# H_BRIDGE.net
KiCad netlist of a schematic drawn in Altium Designer
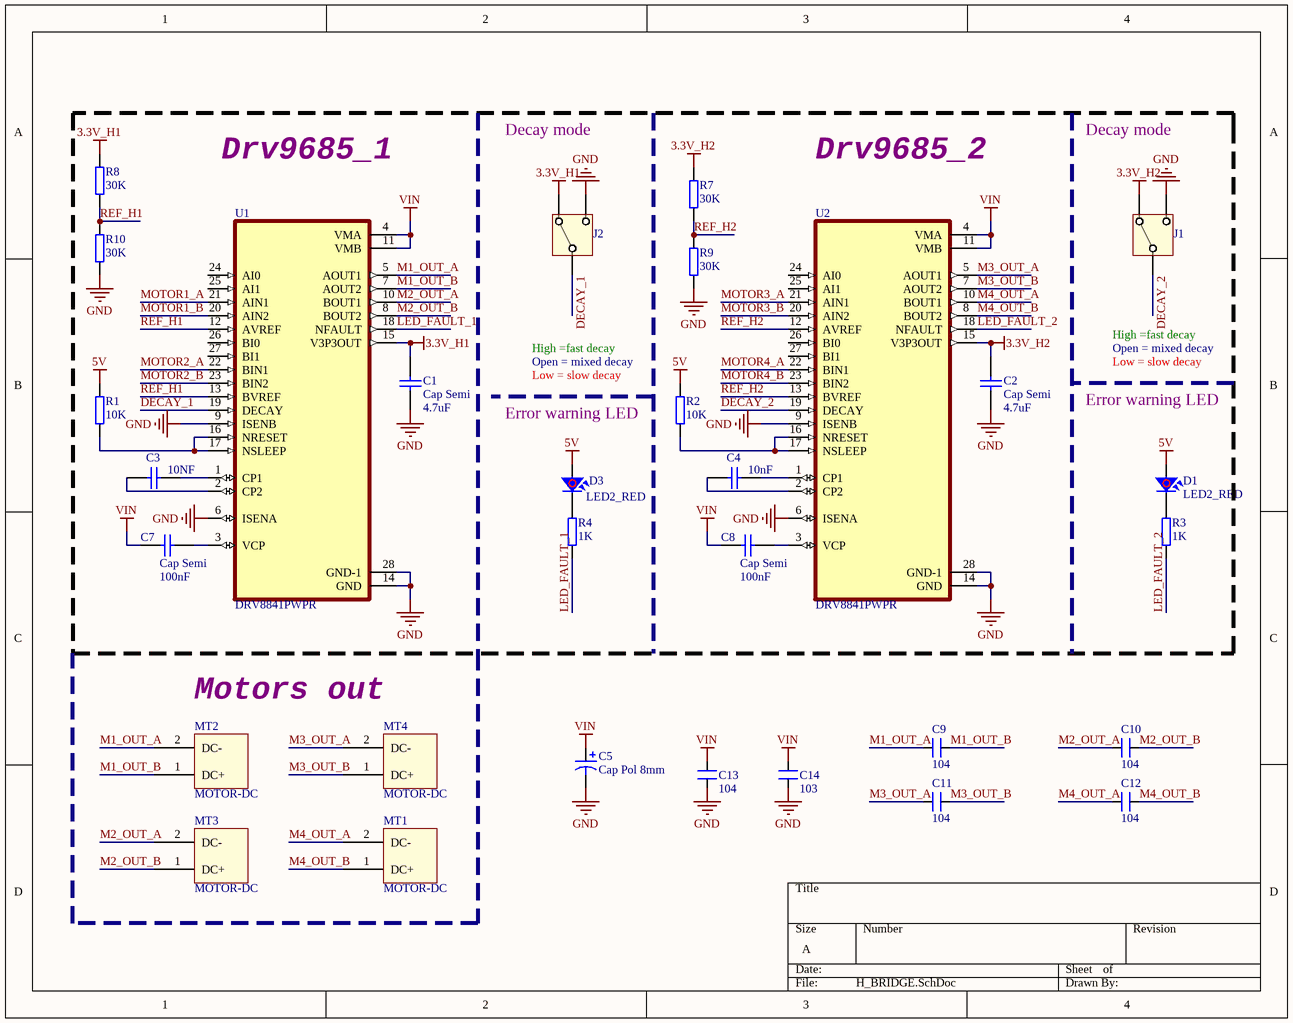
[diagram p0: H_BRIDGE.SchDoc]

(export (version "E")
  (design (tool "Eeschema 10.0.6"))
  (components
    (comp (ref "C1")
      (value "Cap Semi")
      (footprint "SMT0603")
      (description "CAP SM 0603 X5R 4.7uF 10%")
      (fields (field (name "TOLERANCE") "±10%") (field (name "ALTIUM_VALUE") "4.7uF"))
      (libsource (lib "electronpowered") (part "CAP-SM-0603-X5R-4.7uF"))
    )
    (comp (ref "C2")
      (value "Cap Semi")
      (footprint "SMT0603")
      (description "CAP SM 0603 X5R 4.7uF 10%")
      (fields (field (name "TOLERANCE") "±10%") (field (name "ALTIUM_VALUE") "4.7uF"))
      (libsource (lib "electronpowered") (part "CAP-SM-0603-X5R-4.7uF"))
    )
    (comp (ref "C3")
      (value "10NF")
      (footprint "SMT0603")
      (description "CAP SM 0603 X5R 10uF 10%")
      (fields (field (name "TOLERANCE") "±10%") (field (name "Comment") "Cap Semi"))
      (libsource (lib "electronpowered") (part "CAP-SM-0603-X5R-10uF"))
    )
    (comp (ref "C4")
      (value "10nF")
      (footprint "SMT0603")
      (description "CAP SM 0603 X5R 10uF 10%")
      (fields (field (name "TOLERANCE") "±10%") (field (name "Comment") "Cap Semi"))
      (libsource (lib "electronpowered") (part "CAP-SM-0603-X5R-10uF"))
    )
    (comp (ref "C5")
      (value "Cap Pol 8mm")
      (footprint "C10mm")
      (description "Polarized Capacitor (Axial)")
      (fields (field (name "PUBLISHER") "Altium Limited"))
      (libsource (lib "My Library") (part "Cap Pol 8mm"))
    )
    (comp (ref "C7")
      (value "Cap Semi")
      (footprint "SMT0603")
      (description "CAP SM 0603 X7R 100nF 10%")
      (fields (field (name "TOLERANCE") "±10%") (field (name "ALTIUM_VALUE") "100nF"))
      (libsource (lib "electronpowered") (part "CAP-SM-0603-X7R-100nF"))
    )
    (comp (ref "C8")
      (value "Cap Semi")
      (footprint "SMT0603")
      (description "CAP SM 0603 X7R 100nF 10%")
      (fields (field (name "TOLERANCE") "±10%") (field (name "ALTIUM_VALUE") "100nF"))
      (libsource (lib "electronpowered") (part "CAP-SM-0603-X7R-100nF"))
    )
    (comp (ref "C9")
      (value "104")
      (footprint "SM-0805")
      (description "Cap SMD")
      (libsource (lib "My Library") (part "CM"))
    )
    (comp (ref "C10")
      (value "104")
      (footprint "SM-0805")
      (description "Cap SMD")
      (libsource (lib "My Library") (part "CM"))
    )
    (comp (ref "C11")
      (value "104")
      (footprint "SM-0805")
      (description "Cap SMD")
      (libsource (lib "My Library") (part "CM"))
    )
    (comp (ref "C12")
      (value "104")
      (footprint "SM-0805")
      (description "Cap SMD")
      (libsource (lib "My Library") (part "CM"))
    )
    (comp (ref "C13")
      (value "104")
      (footprint "SM-0805")
      (description "Cap SMD")
      (libsource (lib "My Library") (part "CM"))
    )
    (comp (ref "C14")
      (value "103")
      (footprint "SM-0805")
      (description "Cap SMD")
      (libsource (lib "My Library") (part "CM"))
    )
    (comp (ref "D1")
      (value "LED2_RED")
      (footprint "LED_RED_SMD0603")
      (description "LED RED CLEAR 0603 SMD")
      (fields
        (field (name "MANUFACTURER") "Lite-On Inc.")
        (field (name "MANUFACTURER PART NUMBER") "LTST-C191KRKT")
      )
      (libsource (lib "RASHBERRY_EXTERN") (part "LED2_RED-0603/200mA-2V"))
    )
    (comp (ref "D3")
      (value "LED2_RED")
      (footprint "LED_RED_SMD0603")
      (description "LED RED CLEAR 0603 SMD")
      (fields
        (field (name "MANUFACTURER") "Lite-On Inc.")
        (field (name "MANUFACTURER PART NUMBER") "LTST-C191KRKT")
      )
      (libsource (lib "RASHBERRY_EXTERN") (part "LED2_RED-0603/200mA-2V"))
    )
    (comp (ref "J1")
      (value "JUMPER-SOLDER-3WAY-BOTTOM")
      (footprint "JUMPER-SOLDER-3WAY-BOTTOM")
      (libsource (lib "electronpowered") (part "JUMPER-SOLDER-3WAY-BOTTOM"))
    )
    (comp (ref "J2")
      (value "JUMPER-SOLDER-3WAY-BOTTOM")
      (footprint "JUMPER-SOLDER-3WAY-BOTTOM")
      (libsource (lib "electronpowered") (part "JUMPER-SOLDER-3WAY-BOTTOM"))
    )
    (comp (ref "MT1")
      (value "MOTOR-DC")
      (footprint "CON2-5.08DC")
      (libsource (lib "RASHBERRY_EXTERN") (part "MOTOR-DC"))
    )
    (comp (ref "MT2")
      (value "MOTOR-DC")
      (footprint "CON2-5.08DC")
      (libsource (lib "RASHBERRY_EXTERN") (part "MOTOR-DC"))
    )
    (comp (ref "MT3")
      (value "MOTOR-DC")
      (footprint "CON2-5.08DC")
      (libsource (lib "RASHBERRY_EXTERN") (part "MOTOR-DC"))
    )
    (comp (ref "MT4")
      (value "MOTOR-DC")
      (footprint "CON2-5.08DC")
      (libsource (lib "RASHBERRY_EXTERN") (part "MOTOR-DC"))
    )
    (comp (ref "R1")
      (value "10K")
      (footprint "SMT0603")
      (description "RES SM 0603 10K")
      (fields (field (name "Comment") "Resistor"))
      (libsource (lib "electronpowered") (part "RES-SM-0603-10K"))
    )
    (comp (ref "R2")
      (value "10K")
      (footprint "SMT0603")
      (description "RES SM 0603 10K")
      (fields (field (name "Comment") "Resistor"))
      (libsource (lib "electronpowered") (part "RES-SM-0603-10K"))
    )
    (comp (ref "R3")
      (value "1K")
      (footprint "SMT0603")
      (description "RES SM 0603 1K")
      (fields (field (name "Comment") "Resistor"))
      (libsource (lib "electronpowered") (part "RES-SM-0603-1K"))
    )
    (comp (ref "R4")
      (value "1K")
      (footprint "SMT0603")
      (description "RES SM 0603 1K")
      (fields (field (name "Comment") "Resistor"))
      (libsource (lib "electronpowered") (part "RES-SM-0603-1K"))
    )
    (comp (ref "R7")
      (value "30K")
      (footprint "SMT0603")
      (description "RES SM 0603 10K")
      (fields (field (name "Comment") "Resistor"))
      (libsource (lib "electronpowered") (part "RES-SM-0603-10K"))
    )
    (comp (ref "R8")
      (value "30K")
      (footprint "SMT0603")
      (description "RES SM 0603 10K")
      (fields (field (name "Comment") "Resistor"))
      (libsource (lib "electronpowered") (part "RES-SM-0603-10K"))
    )
    (comp (ref "R9")
      (value "30K")
      (footprint "SMT0603")
      (description "RES SM 0603 10K")
      (fields (field (name "Comment") "Resistor"))
      (libsource (lib "electronpowered") (part "RES-SM-0603-10K"))
    )
    (comp (ref "R10")
      (value "30K")
      (footprint "SMT0603")
      (description "RES SM 0603 10K")
      (fields (field (name "Comment") "Resistor"))
      (libsource (lib "electronpowered") (part "RES-SM-0603-10K"))
    )
    (comp (ref "U1")
      (value "DRV8841PWPR")
      (footprint "IC_TPS61196PWPRQ1")
      (libsource (lib "DRV8841PWPR") (part "DRV8841PWPR"))
    )
    (comp (ref "U2")
      (value "DRV8841PWPR")
      (footprint "IC_TPS61196PWPRQ1")
      (libsource (lib "DRV8841PWPR") (part "DRV8841PWPR"))
    )
  )
  (nets
    (net (code "1") (name "/DECAY_1") (class "Default")
      (node (ref "J2") (pin "1") (pinfunction "1_1") (pintype "passive"))
      (node (ref "U1") (pin "19") (pinfunction "DECAY_19") (pintype "input"))
    )
    (net (code "2") (name "/DECAY_2") (class "Default")
      (node (ref "J1") (pin "1") (pinfunction "1_1") (pintype "passive"))
      (node (ref "U2") (pin "19") (pinfunction "DECAY_19") (pintype "input"))
    )
    (net (code "3") (name "/LED_FAULT_1") (class "Default")
      (node (ref "R4") (pin "1") (pinfunction "1_1") (pintype "passive"))
      (node (ref "U1") (pin "18") (pinfunction "NFAULT_18") (pintype "output"))
    )
    (net (code "4") (name "/LED_FAULT_2") (class "Default")
      (node (ref "R3") (pin "1") (pinfunction "1_1") (pintype "passive"))
      (node (ref "U2") (pin "18") (pinfunction "NFAULT_18") (pintype "output"))
    )
    (net (code "5") (name "/M1_OUT_A") (class "Default")
      (node (ref "C9") (pin "2") (pinfunction "2_2") (pintype "passive"))
      (node (ref "MT2") (pin "2") (pinfunction "DC-_2") (pintype "passive"))
      (node (ref "U1") (pin "5") (pinfunction "AOUT1_5") (pintype "output"))
    )
    (net (code "6") (name "/M1_OUT_B") (class "Default")
      (node (ref "C9") (pin "1") (pinfunction "1_1") (pintype "passive"))
      (node (ref "MT2") (pin "1") (pinfunction "DC+_1") (pintype "passive"))
      (node (ref "U1") (pin "7") (pinfunction "AOUT2_7") (pintype "output"))
    )
    (net (code "7") (name "/M2_OUT_A") (class "Default")
      (node (ref "C10") (pin "2") (pinfunction "2_2") (pintype "passive"))
      (node (ref "MT3") (pin "2") (pinfunction "DC-_2") (pintype "passive"))
      (node (ref "U1") (pin "10") (pinfunction "BOUT1_10") (pintype "output"))
    )
    (net (code "8") (name "/M2_OUT_B") (class "Default")
      (node (ref "C10") (pin "1") (pinfunction "1_1") (pintype "passive"))
      (node (ref "MT3") (pin "1") (pinfunction "DC+_1") (pintype "passive"))
      (node (ref "U1") (pin "8") (pinfunction "BOUT2_8") (pintype "output"))
    )
    (net (code "9") (name "/M3_OUT_A") (class "Default")
      (node (ref "C11") (pin "2") (pinfunction "2_2") (pintype "passive"))
      (node (ref "MT4") (pin "2") (pinfunction "DC-_2") (pintype "passive"))
      (node (ref "U2") (pin "5") (pinfunction "AOUT1_5") (pintype "output"))
    )
    (net (code "10") (name "/M3_OUT_B") (class "Default")
      (node (ref "C11") (pin "1") (pinfunction "1_1") (pintype "passive"))
      (node (ref "MT4") (pin "1") (pinfunction "DC+_1") (pintype "passive"))
      (node (ref "U2") (pin "7") (pinfunction "AOUT2_7") (pintype "output"))
    )
    (net (code "11") (name "/M4_OUT_A") (class "Default")
      (node (ref "C12") (pin "2") (pinfunction "2_2") (pintype "passive"))
      (node (ref "MT1") (pin "2") (pinfunction "DC-_2") (pintype "passive"))
      (node (ref "U2") (pin "10") (pinfunction "BOUT1_10") (pintype "output"))
    )
    (net (code "12") (name "/M4_OUT_B") (class "Default")
      (node (ref "C12") (pin "1") (pinfunction "1_1") (pintype "passive"))
      (node (ref "MT1") (pin "1") (pinfunction "DC+_1") (pintype "passive"))
      (node (ref "U2") (pin "8") (pinfunction "BOUT2_8") (pintype "output"))
    )
    (net (code "13") (name "/MOTOR1_A") (class "Default")
      (node (ref "U1") (pin "21") (pinfunction "AIN1_21") (pintype "input"))
    )
    (net (code "14") (name "/MOTOR1_B") (class "Default")
      (node (ref "U1") (pin "20") (pinfunction "AIN2_20") (pintype "input"))
    )
    (net (code "15") (name "/MOTOR2_A") (class "Default")
      (node (ref "U1") (pin "22") (pinfunction "BIN1_22") (pintype "input"))
    )
    (net (code "16") (name "/MOTOR2_B") (class "Default")
      (node (ref "U1") (pin "23") (pinfunction "BIN2_23") (pintype "input"))
    )
    (net (code "17") (name "/MOTOR3_A") (class "Default")
      (node (ref "U2") (pin "21") (pinfunction "AIN1_21") (pintype "input"))
    )
    (net (code "18") (name "/MOTOR3_B") (class "Default")
      (node (ref "U2") (pin "20") (pinfunction "AIN2_20") (pintype "input"))
    )
    (net (code "19") (name "/MOTOR4_A") (class "Default")
      (node (ref "U2") (pin "22") (pinfunction "BIN1_22") (pintype "input"))
    )
    (net (code "20") (name "/MOTOR4_B") (class "Default")
      (node (ref "U2") (pin "23") (pinfunction "BIN2_23") (pintype "input"))
    )
    (net (code "21") (name "/REF_H1") (class "Default")
      (node (ref "R10") (pin "2") (pinfunction "2_2") (pintype "passive"))
      (node (ref "R8") (pin "1") (pinfunction "1_1") (pintype "passive"))
      (node (ref "U1") (pin "12") (pinfunction "AVREF_12") (pintype "input"))
      (node (ref "U1") (pin "13") (pinfunction "BVREF_13") (pintype "input"))
    )
    (net (code "22") (name "/REF_H2") (class "Default")
      (node (ref "R7") (pin "1") (pinfunction "1_1") (pintype "passive"))
      (node (ref "R9") (pin "2") (pinfunction "2_2") (pintype "passive"))
      (node (ref "U2") (pin "12") (pinfunction "AVREF_12") (pintype "input"))
      (node (ref "U2") (pin "13") (pinfunction "BVREF_13") (pintype "input"))
    )
    (net (code "23") (name "3.3V_H1") (class "Default")
      (node (ref "C1") (pin "2") (pinfunction "2_2") (pintype "passive"))
      (node (ref "J2") (pin "0") (pinfunction "0_0") (pintype "passive"))
      (node (ref "R8") (pin "2") (pinfunction "2_2") (pintype "passive"))
      (node (ref "U1") (pin "15") (pinfunction "V3P3OUT_15") (pintype "output"))
    )
    (net (code "24") (name "3.3V_H2") (class "Default")
      (node (ref "C2") (pin "2") (pinfunction "2_2") (pintype "passive"))
      (node (ref "J1") (pin "0") (pinfunction "0_0") (pintype "passive"))
      (node (ref "R7") (pin "2") (pinfunction "2_2") (pintype "passive"))
      (node (ref "U2") (pin "15") (pinfunction "V3P3OUT_15") (pintype "output"))
    )
    (net (code "25") (name "5V") (class "Default")
      (node (ref "D1") (pin "1") (pinfunction "1_1") (pintype "passive"))
      (node (ref "D3") (pin "1") (pinfunction "1_1") (pintype "passive"))
      (node (ref "R1") (pin "2") (pinfunction "2_2") (pintype "passive"))
      (node (ref "R2") (pin "2") (pinfunction "2_2") (pintype "passive"))
    )
    (net (code "26") (name "GND") (class "Default")
      (node (ref "C1") (pin "1") (pinfunction "1_1") (pintype "passive"))
      (node (ref "C13") (pin "1") (pinfunction "1_1") (pintype "passive"))
      (node (ref "C14") (pin "1") (pinfunction "1_1") (pintype "passive"))
      (node (ref "C2") (pin "1") (pinfunction "1_1") (pintype "passive"))
      (node (ref "C5") (pin "2") (pinfunction "2_2") (pintype "passive"))
      (node (ref "J1") (pin "2") (pinfunction "2_2") (pintype "passive"))
      (node (ref "J2") (pin "2") (pinfunction "2_2") (pintype "passive"))
      (node (ref "R10") (pin "1") (pinfunction "1_1") (pintype "passive"))
      (node (ref "R9") (pin "1") (pinfunction "1_1") (pintype "passive"))
      (node (ref "U1") (pin "14") (pinfunction "GND_14") (pintype "power_in"))
      (node (ref "U1") (pin "28") (pinfunction "GND-1_28") (pintype "power_in"))
      (node (ref "U1") (pin "6") (pinfunction "ISENA_6") (pintype "bidirectional"))
      (node (ref "U1") (pin "9") (pinfunction "ISENB_9") (pintype "input"))
      (node (ref "U2") (pin "14") (pinfunction "GND_14") (pintype "power_in"))
      (node (ref "U2") (pin "28") (pinfunction "GND-1_28") (pintype "power_in"))
      (node (ref "U2") (pin "6") (pinfunction "ISENA_6") (pintype "bidirectional"))
      (node (ref "U2") (pin "9") (pinfunction "ISENB_9") (pintype "input"))
    )
    (net (code "27") (name "Net-(D1-Pad2)") (class "Default")
      (node (ref "D1") (pin "2") (pinfunction "2_2") (pintype "passive"))
      (node (ref "R3") (pin "2") (pinfunction "2_2") (pintype "passive"))
    )
    (net (code "28") (name "Net-(D3-Pad2)") (class "Default")
      (node (ref "D3") (pin "2") (pinfunction "2_2") (pintype "passive"))
      (node (ref "R4") (pin "2") (pinfunction "2_2") (pintype "passive"))
    )
    (net (code "29") (name "Net-(U1-CP1)") (class "Default")
      (node (ref "C3") (pin "2") (pinfunction "2_2") (pintype "passive"))
      (node (ref "U1") (pin "1") (pinfunction "CP1_1") (pintype "bidirectional"))
    )
    (net (code "30") (name "Net-(U1-CP2)") (class "Default")
      (node (ref "C3") (pin "1") (pinfunction "1_1") (pintype "passive"))
      (node (ref "U1") (pin "2") (pinfunction "CP2_2") (pintype "bidirectional"))
    )
    (net (code "31") (name "Net-(U1-NRESET)") (class "Default")
      (node (ref "R1") (pin "1") (pinfunction "1_1") (pintype "passive"))
      (node (ref "U1") (pin "16") (pinfunction "NRESET_16") (pintype "input"))
      (node (ref "U1") (pin "17") (pinfunction "NSLEEP_17") (pintype "input"))
    )
    (net (code "32") (name "Net-(U1-VCP)") (class "Default")
      (node (ref "C7") (pin "2") (pinfunction "2_2") (pintype "passive"))
      (node (ref "U1") (pin "3") (pinfunction "VCP_3") (pintype "bidirectional"))
    )
    (net (code "33") (name "Net-(U2-CP1)") (class "Default")
      (node (ref "C4") (pin "2") (pinfunction "2_2") (pintype "passive"))
      (node (ref "U2") (pin "1") (pinfunction "CP1_1") (pintype "bidirectional"))
    )
    (net (code "34") (name "Net-(U2-CP2)") (class "Default")
      (node (ref "C4") (pin "1") (pinfunction "1_1") (pintype "passive"))
      (node (ref "U2") (pin "2") (pinfunction "CP2_2") (pintype "bidirectional"))
    )
    (net (code "35") (name "Net-(U2-NRESET)") (class "Default")
      (node (ref "R2") (pin "1") (pinfunction "1_1") (pintype "passive"))
      (node (ref "U2") (pin "16") (pinfunction "NRESET_16") (pintype "input"))
      (node (ref "U2") (pin "17") (pinfunction "NSLEEP_17") (pintype "input"))
    )
    (net (code "36") (name "Net-(U2-VCP)") (class "Default")
      (node (ref "C8") (pin "2") (pinfunction "2_2") (pintype "passive"))
      (node (ref "U2") (pin "3") (pinfunction "VCP_3") (pintype "bidirectional"))
    )
    (net (code "37") (name "VIN") (class "Default")
      (node (ref "C13") (pin "2") (pinfunction "2_2") (pintype "passive"))
      (node (ref "C14") (pin "2") (pinfunction "2_2") (pintype "passive"))
      (node (ref "C5") (pin "1") (pinfunction "1_1") (pintype "passive"))
      (node (ref "C7") (pin "1") (pinfunction "1_1") (pintype "passive"))
      (node (ref "C8") (pin "1") (pinfunction "1_1") (pintype "passive"))
      (node (ref "U1") (pin "11") (pinfunction "VMB_11") (pintype "power_in"))
      (node (ref "U1") (pin "4") (pinfunction "VMA_4") (pintype "power_in"))
      (node (ref "U2") (pin "11") (pinfunction "VMB_11") (pintype "power_in"))
      (node (ref "U2") (pin "4") (pinfunction "VMA_4") (pintype "power_in"))
    )
    (net (code "38") (name "unconnected-(U1-AI0-Pad24)") (class "Default")
      (node (ref "U1") (pin "24") (pinfunction "AI0_24") (pintype "input"))
    )
    (net (code "39") (name "unconnected-(U1-AI1-Pad25)") (class "Default")
      (node (ref "U1") (pin "25") (pinfunction "AI1_25") (pintype "input"))
    )
    (net (code "40") (name "unconnected-(U1-BI0-Pad26)") (class "Default")
      (node (ref "U1") (pin "26") (pinfunction "BI0_26") (pintype "input"))
    )
    (net (code "41") (name "unconnected-(U1-BI1-Pad27)") (class "Default")
      (node (ref "U1") (pin "27") (pinfunction "BI1_27") (pintype "input"))
    )
    (net (code "42") (name "unconnected-(U2-AI0-Pad24)") (class "Default")
      (node (ref "U2") (pin "24") (pinfunction "AI0_24") (pintype "input"))
    )
    (net (code "43") (name "unconnected-(U2-AI1-Pad25)") (class "Default")
      (node (ref "U2") (pin "25") (pinfunction "AI1_25") (pintype "input"))
    )
    (net (code "44") (name "unconnected-(U2-BI0-Pad26)") (class "Default")
      (node (ref "U2") (pin "26") (pinfunction "BI0_26") (pintype "input"))
    )
    (net (code "45") (name "unconnected-(U2-BI1-Pad27)") (class "Default")
      (node (ref "U2") (pin "27") (pinfunction "BI1_27") (pintype "input"))
    )
  )
)
